# atmega8.net
KiCad netlist of a schematic drawn in EAGLE
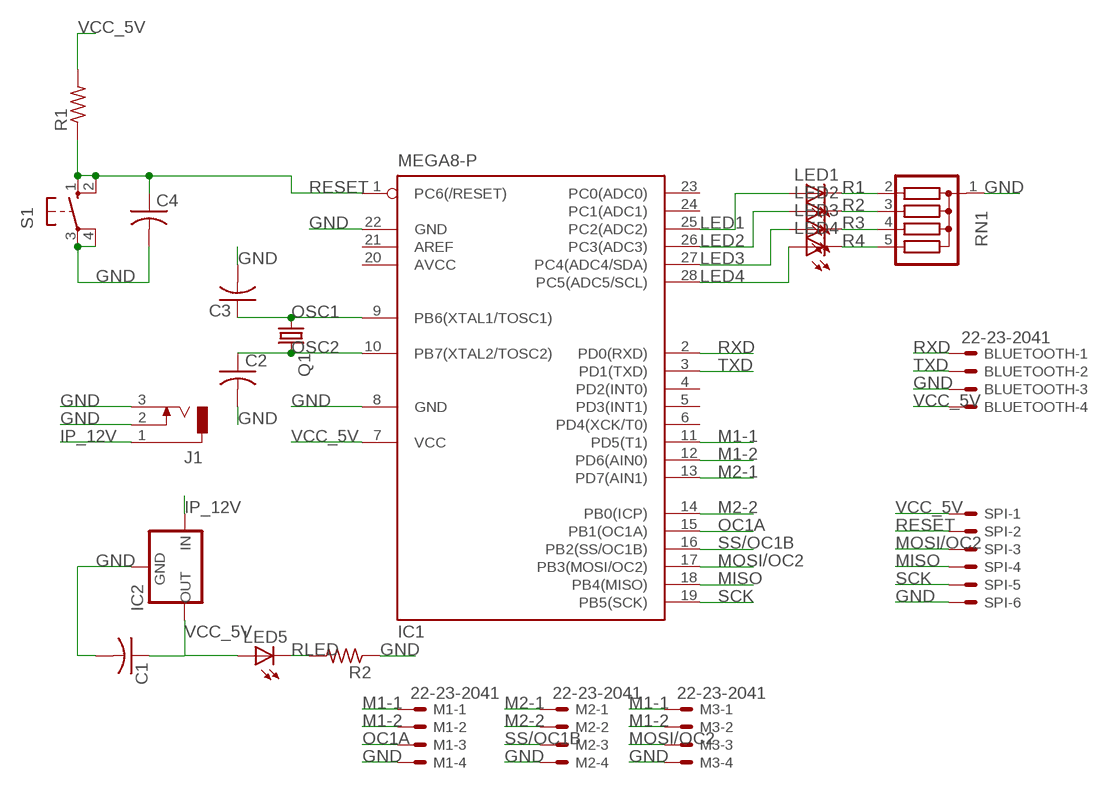
[diagram p0: schematic, sheet 1]

(export (version "E")
  (design (tool "Eeschema 10.0.6"))
  (components
    (comp (ref "BLUETOOTH")
      (value "22-23-2041")
      (footprint "eagle-import:22-23-2041")
      (fields (field (name "MF") "MOLEX"))
      (libsource (lib "eagle-import") (part "22-23-2041"))
    )
    (comp (ref "C1")
      (value "C-US050-025X075")
      (footprint "eagle-import:C050-025X075")
      (libsource (lib "eagle-import") (part "C-US050-025X075"))
    )
    (comp (ref "C2")
      (value "C-US050-025X075")
      (footprint "eagle-import:C050-025X075")
      (libsource (lib "eagle-import") (part "C-US050-025X075"))
    )
    (comp (ref "C3")
      (value "C-US050-025X075")
      (footprint "eagle-import:C050-025X075")
      (libsource (lib "eagle-import") (part "C-US050-025X075"))
    )
    (comp (ref "C4")
      (value "C-US050-025X075")
      (footprint "eagle-import:C050-025X075")
      (libsource (lib "eagle-import") (part "C-US050-025X075"))
    )
    (comp (ref "IC1")
      (value "MEGA8-P")
      (footprint "eagle-import:DIL28-3")
      (libsource (lib "eagle-import") (part "MEGA8-P"))
    )
    (comp (ref "IC2")
      (value "78XXL")
      (footprint "eagle-import:78XXL")
      (libsource (lib "eagle-import") (part "78XXL"))
    )
    (comp (ref "J1")
      (value "DCJ0303")
      (footprint "eagle-import:DCJ0303")
      (libsource (lib "eagle-import") (part "DCJ0303"))
    )
    (comp (ref "LED1")
      (value "LED3MM")
      (footprint "eagle-import:LED3MM")
      (libsource (lib "eagle-import") (part "LED3MM"))
    )
    (comp (ref "LED2")
      (value "LED3MM")
      (footprint "eagle-import:LED3MM")
      (libsource (lib "eagle-import") (part "LED3MM"))
    )
    (comp (ref "LED3")
      (value "LED3MM")
      (footprint "eagle-import:LED3MM")
      (libsource (lib "eagle-import") (part "LED3MM"))
    )
    (comp (ref "LED4")
      (value "LED3MM")
      (footprint "eagle-import:LED3MM")
      (libsource (lib "eagle-import") (part "LED3MM"))
    )
    (comp (ref "LED5")
      (value "LED3MM")
      (footprint "eagle-import:LED3MM")
      (libsource (lib "eagle-import") (part "LED3MM"))
    )
    (comp (ref "M1")
      (value "22-23-2041")
      (footprint "eagle-import:22-23-2041")
      (fields (field (name "MF") "MOLEX"))
      (libsource (lib "eagle-import") (part "22-23-2041"))
    )
    (comp (ref "M2")
      (value "22-23-2041")
      (footprint "eagle-import:22-23-2041")
      (fields (field (name "MF") "MOLEX"))
      (libsource (lib "eagle-import") (part "22-23-2041"))
    )
    (comp (ref "M3")
      (value "22-23-2041")
      (footprint "eagle-import:22-23-2041")
      (fields (field (name "MF") "MOLEX"))
      (libsource (lib "eagle-import") (part "22-23-2041"))
    )
    (comp (ref "Q1")
      (value "CRYSTALHC18U-V")
      (footprint "eagle-import:HC18U-V")
      (libsource (lib "eagle-import") (part "CRYSTALHC18U-V"))
    )
    (comp (ref "R1")
      (value "R-US_0204/7")
      (footprint "eagle-import:0204_7")
      (libsource (lib "eagle-import") (part "R-US_0204/7"))
    )
    (comp (ref "R2")
      (value "R-US_0204/7")
      (footprint "eagle-import:0204_7")
      (libsource (lib "eagle-import") (part "R-US_0204/7"))
    )
    (comp (ref "RN1")
      (value "G04R")
      (footprint "eagle-import:SIL5")
      (libsource (lib "eagle-import") (part "G04R"))
    )
    (comp (ref "S1")
      (value "10-XX")
      (footprint "eagle-import:B3F-10XX")
      (fields (field (name "MPN") "B3F-1000"))
      (libsource (lib "eagle-import") (part "10-XX"))
    )
    (comp (ref "SPI")
      (value "22-23-2061")
      (footprint "eagle-import:22-23-2061")
      (fields (field (name "MF") "MOLEX"))
      (libsource (lib "eagle-import") (part "22-23-2061"))
    )
  )
  (nets
    (net (code "1") (name "/AVCC") (class "Default")
      (node (ref "IC1") (pin "20") (pinfunction "AVCC_20") (pintype "power_in"))
    )
    (net (code "2") (name "/GND") (class "Default")
      (node (ref "BLUETOOTH") (pin "3") (pinfunction "S_3") (pintype "passive"))
      (node (ref "C1") (pin "2") (pinfunction "2_2") (pintype "passive"))
      (node (ref "C2") (pin "2") (pinfunction "2_2") (pintype "passive"))
      (node (ref "C3") (pin "2") (pinfunction "2_2") (pintype "passive"))
      (node (ref "C4") (pin "2") (pinfunction "2_2") (pintype "passive"))
      (node (ref "IC1") (pin "22") (pinfunction "GND_22") (pintype "power_in"))
      (node (ref "IC1") (pin "8") (pinfunction "GND_8") (pintype "power_in"))
      (node (ref "IC2") (pin "GND") (pinfunction "GND_GND") (pintype "input"))
      (node (ref "J1") (pin "2") (pinfunction "2_2") (pintype "passive"))
      (node (ref "J1") (pin "3") (pinfunction "3_3") (pintype "passive"))
      (node (ref "M1") (pin "4") (pinfunction "S_4") (pintype "passive"))
      (node (ref "M2") (pin "4") (pinfunction "S_4") (pintype "passive"))
      (node (ref "M3") (pin "4") (pinfunction "S_4") (pintype "passive"))
      (node (ref "R2") (pin "1") (pinfunction "1_1") (pintype "passive"))
      (node (ref "RN1") (pin "1") (pinfunction "1_1") (pintype "passive"))
      (node (ref "S1") (pin "3") (pinfunction "P_3") (pintype "passive"))
      (node (ref "S1") (pin "4") (pinfunction "P1_4") (pintype "passive"))
      (node (ref "SPI") (pin "6") (pinfunction "S_6") (pintype "passive"))
    )
    (net (code "3") (name "/IP_12V") (class "Default")
      (node (ref "IC2") (pin "IN") (pinfunction "IN_IN") (pintype "input"))
      (node (ref "J1") (pin "1") (pinfunction "1_1") (pintype "passive"))
    )
    (net (code "4") (name "/LED1") (class "Default")
      (node (ref "IC1") (pin "25") (pinfunction "PC2(ADC2)_25") (pintype "bidirectional"))
      (node (ref "LED1") (pin "A") (pinfunction "A_A") (pintype "passive"))
    )
    (net (code "5") (name "/LED2") (class "Default")
      (node (ref "IC1") (pin "26") (pinfunction "PC3(ADC3)_26") (pintype "bidirectional"))
      (node (ref "LED2") (pin "A") (pinfunction "A_A") (pintype "passive"))
    )
    (net (code "6") (name "/LED3") (class "Default")
      (node (ref "IC1") (pin "27") (pinfunction "PC4(ADC4/SDA)_27") (pintype "bidirectional"))
      (node (ref "LED3") (pin "A") (pinfunction "A_A") (pintype "passive"))
    )
    (net (code "7") (name "/LED4") (class "Default")
      (node (ref "IC1") (pin "28") (pinfunction "PC5(ADC5/SCL)_28") (pintype "bidirectional"))
      (node (ref "LED4") (pin "A") (pinfunction "A_A") (pintype "passive"))
    )
    (net (code "8") (name "/M1-1") (class "Default")
      (node (ref "IC1") (pin "11") (pinfunction "PD5(T1)_11") (pintype "bidirectional"))
      (node (ref "M1") (pin "1") (pinfunction "S_1") (pintype "passive"))
      (node (ref "M3") (pin "1") (pinfunction "S_1") (pintype "passive"))
    )
    (net (code "9") (name "/M1-2") (class "Default")
      (node (ref "IC1") (pin "12") (pinfunction "PD6(AIN0)_12") (pintype "bidirectional"))
      (node (ref "M1") (pin "2") (pinfunction "S_2") (pintype "passive"))
      (node (ref "M3") (pin "2") (pinfunction "S_2") (pintype "passive"))
    )
    (net (code "10") (name "/M2-1") (class "Default")
      (node (ref "IC1") (pin "13") (pinfunction "PD7(AIN1)_13") (pintype "bidirectional"))
      (node (ref "M2") (pin "1") (pinfunction "S_1") (pintype "passive"))
    )
    (net (code "11") (name "/M2-2") (class "Default")
      (node (ref "IC1") (pin "14") (pinfunction "PB0(ICP)_14") (pintype "bidirectional"))
      (node (ref "M2") (pin "2") (pinfunction "S_2") (pintype "passive"))
    )
    (net (code "12") (name "/MISO") (class "Default")
      (node (ref "IC1") (pin "18") (pinfunction "PB4(MISO)_18") (pintype "bidirectional"))
      (node (ref "SPI") (pin "4") (pinfunction "S_4") (pintype "passive"))
    )
    (net (code "13") (name "/MOSI{slash}OC2") (class "Default")
      (node (ref "IC1") (pin "17") (pinfunction "PB3(MOSI/OC2)_17") (pintype "bidirectional"))
      (node (ref "M3") (pin "3") (pinfunction "S_3") (pintype "passive"))
      (node (ref "SPI") (pin "3") (pinfunction "S_3") (pintype "passive"))
    )
    (net (code "14") (name "/OC1A") (class "Default")
      (node (ref "IC1") (pin "15") (pinfunction "PB1(OC1A)_15") (pintype "bidirectional"))
      (node (ref "M1") (pin "3") (pinfunction "S_3") (pintype "passive"))
    )
    (net (code "15") (name "/OSC1") (class "Default")
      (node (ref "C3") (pin "1") (pinfunction "1_1") (pintype "passive"))
      (node (ref "IC1") (pin "9") (pinfunction "PB6(XTAL1/TOSC1)_9") (pintype "bidirectional"))
      (node (ref "Q1") (pin "1") (pinfunction "1_1") (pintype "passive"))
    )
    (net (code "16") (name "/OSC2") (class "Default")
      (node (ref "C2") (pin "1") (pinfunction "1_1") (pintype "passive"))
      (node (ref "IC1") (pin "10") (pinfunction "PB7(XTAL2/TOSC2)_10") (pintype "bidirectional"))
      (node (ref "Q1") (pin "2") (pinfunction "2_2") (pintype "passive"))
    )
    (net (code "17") (name "/R1") (class "Default")
      (node (ref "LED1") (pin "K") (pinfunction "C_K") (pintype "passive"))
      (node (ref "RN1") (pin "2") (pinfunction "2_2") (pintype "passive"))
    )
    (net (code "18") (name "/R2") (class "Default")
      (node (ref "LED2") (pin "K") (pinfunction "C_K") (pintype "passive"))
      (node (ref "RN1") (pin "3") (pinfunction "3_3") (pintype "passive"))
    )
    (net (code "19") (name "/R3") (class "Default")
      (node (ref "LED3") (pin "K") (pinfunction "C_K") (pintype "passive"))
      (node (ref "RN1") (pin "4") (pinfunction "4_4") (pintype "passive"))
    )
    (net (code "20") (name "/R4") (class "Default")
      (node (ref "LED4") (pin "K") (pinfunction "C_K") (pintype "passive"))
      (node (ref "RN1") (pin "5") (pinfunction "5_5") (pintype "passive"))
    )
    (net (code "21") (name "/RESET") (class "Default")
      (node (ref "C4") (pin "1") (pinfunction "1_1") (pintype "passive"))
      (node (ref "IC1") (pin "1") (pinfunction "PC6(/RESET)_1") (pintype "bidirectional"))
      (node (ref "R1") (pin "1") (pinfunction "1_1") (pintype "passive"))
      (node (ref "S1") (pin "1") (pinfunction "S_1") (pintype "passive"))
      (node (ref "S1") (pin "2") (pinfunction "S1_2") (pintype "passive"))
      (node (ref "SPI") (pin "2") (pinfunction "S_2") (pintype "passive"))
    )
    (net (code "22") (name "/RLED") (class "Default")
      (node (ref "LED5") (pin "K") (pinfunction "C_K") (pintype "passive"))
      (node (ref "R2") (pin "2") (pinfunction "2_2") (pintype "passive"))
    )
    (net (code "23") (name "/RXD") (class "Default")
      (node (ref "BLUETOOTH") (pin "1") (pinfunction "S_1") (pintype "passive"))
      (node (ref "IC1") (pin "2") (pinfunction "PD0(RXD)_2") (pintype "bidirectional"))
    )
    (net (code "24") (name "/SCK") (class "Default")
      (node (ref "IC1") (pin "19") (pinfunction "PB5(SCK)_19") (pintype "bidirectional"))
      (node (ref "SPI") (pin "5") (pinfunction "S_5") (pintype "passive"))
    )
    (net (code "25") (name "/SS{slash}OC1B") (class "Default")
      (node (ref "IC1") (pin "16") (pinfunction "PB2(SS/OC1B)_16") (pintype "bidirectional"))
      (node (ref "M2") (pin "3") (pinfunction "S_3") (pintype "passive"))
    )
    (net (code "26") (name "/TXD") (class "Default")
      (node (ref "BLUETOOTH") (pin "2") (pinfunction "S_2") (pintype "passive"))
      (node (ref "IC1") (pin "3") (pinfunction "PD1(TXD)_3") (pintype "bidirectional"))
    )
    (net (code "27") (name "/VCC_5V") (class "Default")
      (node (ref "BLUETOOTH") (pin "4") (pinfunction "S_4") (pintype "passive"))
      (node (ref "C1") (pin "1") (pinfunction "1_1") (pintype "passive"))
      (node (ref "IC1") (pin "7") (pinfunction "VCC_7") (pintype "power_in"))
      (node (ref "IC2") (pin "OUT") (pinfunction "OUT_OUT") (pintype "passive"))
      (node (ref "LED5") (pin "A") (pinfunction "A_A") (pintype "passive"))
      (node (ref "R1") (pin "2") (pinfunction "2_2") (pintype "passive"))
      (node (ref "SPI") (pin "1") (pinfunction "S_1") (pintype "passive"))
    )
    (net (code "28") (name "unconnected-(IC1-AREF-Pad21)") (class "Default")
      (node (ref "IC1") (pin "21") (pinfunction "AREF_21") (pintype "passive"))
    )
    (net (code "29") (name "unconnected-(IC1-PC0(ADC0)-Pad23)") (class "Default")
      (node (ref "IC1") (pin "23") (pinfunction "PC0(ADC0)_23") (pintype "bidirectional"))
    )
    (net (code "30") (name "unconnected-(IC1-PC1(ADC1)-Pad24)") (class "Default")
      (node (ref "IC1") (pin "24") (pinfunction "PC1(ADC1)_24") (pintype "bidirectional"))
    )
    (net (code "31") (name "unconnected-(IC1-PD2(INT0)-Pad4)") (class "Default")
      (node (ref "IC1") (pin "4") (pinfunction "PD2(INT0)_4") (pintype "bidirectional"))
    )
    (net (code "32") (name "unconnected-(IC1-PD3(INT1)-Pad5)") (class "Default")
      (node (ref "IC1") (pin "5") (pinfunction "PD3(INT1)_5") (pintype "bidirectional"))
    )
    (net (code "33") (name "unconnected-(IC1-PD4(XCK{slash}T0)-Pad6)") (class "Default")
      (node (ref "IC1") (pin "6") (pinfunction "PD4(XCK/T0)_6") (pintype "bidirectional"))
    )
  )
)
